# anemometerMv1.net
KiCad netlist of a schematic drawn in EAGLE
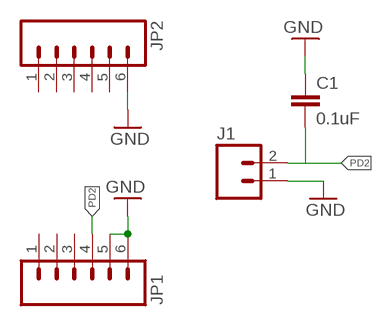
[diagram p0: schematic, sheet 1]

(export (version "E")
  (design (tool "Eeschema 10.0.6"))
  (components
    (comp (ref "C1")
      (value "0.1uF")
      (footprint "eagle-import:0805-CAP")
      (libsource (lib "eagle-import") (part "0.33UF-50V-10%(0805)"))
    )
    (comp (ref "J1")
      (value "M02LOCK_LONGPADS")
      (footprint "eagle-import:1X02_LOCK_LONGPADS")
      (libsource (lib "eagle-import") (part "M02LOCK_LONGPADS"))
    )
    (comp (ref "JP1")
      (value "M06LOCK_LONGPADS")
      (footprint "eagle-import:1X06_LOCK_LONGPADS")
      (libsource (lib "eagle-import") (part "M06LOCK_LONGPADS"))
    )
    (comp (ref "JP2")
      (value "M06LOCK_LONGPADS")
      (footprint "eagle-import:1X06_LOCK_LONGPADS")
      (libsource (lib "eagle-import") (part "M06LOCK_LONGPADS"))
    )
  )
  (nets
    (net (code "1") (name "GND") (class "Default")
      (node (ref "C1") (pin "1") (pinfunction "1_1") (pintype "passive"))
      (node (ref "J1") (pin "1") (pinfunction "1_1") (pintype "passive"))
      (node (ref "JP1") (pin "5") (pinfunction "5_5") (pintype "passive"))
      (node (ref "JP1") (pin "6") (pinfunction "6_6") (pintype "passive"))
      (node (ref "JP2") (pin "6") (pinfunction "6_6") (pintype "passive"))
    )
    (net (code "2") (name "PD2") (class "Default")
      (node (ref "C1") (pin "2") (pinfunction "2_2") (pintype "passive"))
      (node (ref "J1") (pin "2") (pinfunction "2_2") (pintype "passive"))
      (node (ref "JP1") (pin "4") (pinfunction "4_4") (pintype "passive"))
    )
    (net (code "3") (name "unconnected-(JP1-Pad1)") (class "Default")
      (node (ref "JP1") (pin "1") (pinfunction "1_1") (pintype "passive"))
    )
    (net (code "4") (name "unconnected-(JP1-Pad2)") (class "Default")
      (node (ref "JP1") (pin "2") (pinfunction "2_2") (pintype "passive"))
    )
    (net (code "5") (name "unconnected-(JP1-Pad3)") (class "Default")
      (node (ref "JP1") (pin "3") (pinfunction "3_3") (pintype "passive"))
    )
    (net (code "6") (name "unconnected-(JP2-Pad1)") (class "Default")
      (node (ref "JP2") (pin "1") (pinfunction "1_1") (pintype "passive"))
    )
    (net (code "7") (name "unconnected-(JP2-Pad2)") (class "Default")
      (node (ref "JP2") (pin "2") (pinfunction "2_2") (pintype "passive"))
    )
    (net (code "8") (name "unconnected-(JP2-Pad3)") (class "Default")
      (node (ref "JP2") (pin "3") (pinfunction "3_3") (pintype "passive"))
    )
    (net (code "9") (name "unconnected-(JP2-Pad4)") (class "Default")
      (node (ref "JP2") (pin "4") (pinfunction "4_4") (pintype "passive"))
    )
    (net (code "10") (name "unconnected-(JP2-Pad5)") (class "Default")
      (node (ref "JP2") (pin "5") (pinfunction "5_5") (pintype "passive"))
    )
  )
)
